# MicroToggleSwitch.net
KiCad netlist of a schematic drawn in EAGLE
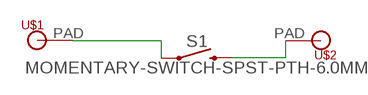
[diagram p0: schematic, sheet 1]

(export (version "E")
  (design (tool "Eeschema 10.0.6"))
  (components
    (comp (ref "S1")
      (value "MOMENTARY-SWITCH-SPST-PTH-6.0MM")
      (footprint "eagle-import:TACTILE_SWITCH_PTH_6.0MM")
      (libsource (lib "eagle-import") (part "MOMENTARY-SWITCH-SPST-PTH-6.0MM"))
    )
    (comp (ref "U$1")
      (value "MICROBIT_PAD")
      (footprint "eagle-import:MICROBIT_PAD")
      (libsource (lib "eagle-import") (part "MICROBIT_PAD"))
    )
    (comp (ref "U$2")
      (value "MICROBIT_PAD")
      (footprint "eagle-import:MICROBIT_PAD")
      (libsource (lib "eagle-import") (part "MICROBIT_PAD"))
    )
  )
  (nets
    (net (code "1") (name "Net-(S1-2)") (class "Default")
      (node (ref "S1") (pin "3") (pinfunction "2_3") (pintype "passive"))
      (node (ref "U$2") (pin "PAD") (pinfunction "P$1_PAD") (pintype "bidirectional"))
    )
    (net (code "2") (name "Net-(U$1-P$1)") (class "Default")
      (node (ref "S1") (pin "1") (pinfunction "1_1") (pintype "passive"))
      (node (ref "U$1") (pin "PAD") (pinfunction "P$1_PAD") (pintype "bidirectional"))
    )
  )
)
